# driver_power_AC.net
KiCad netlist of a schematic drawn in EAGLE
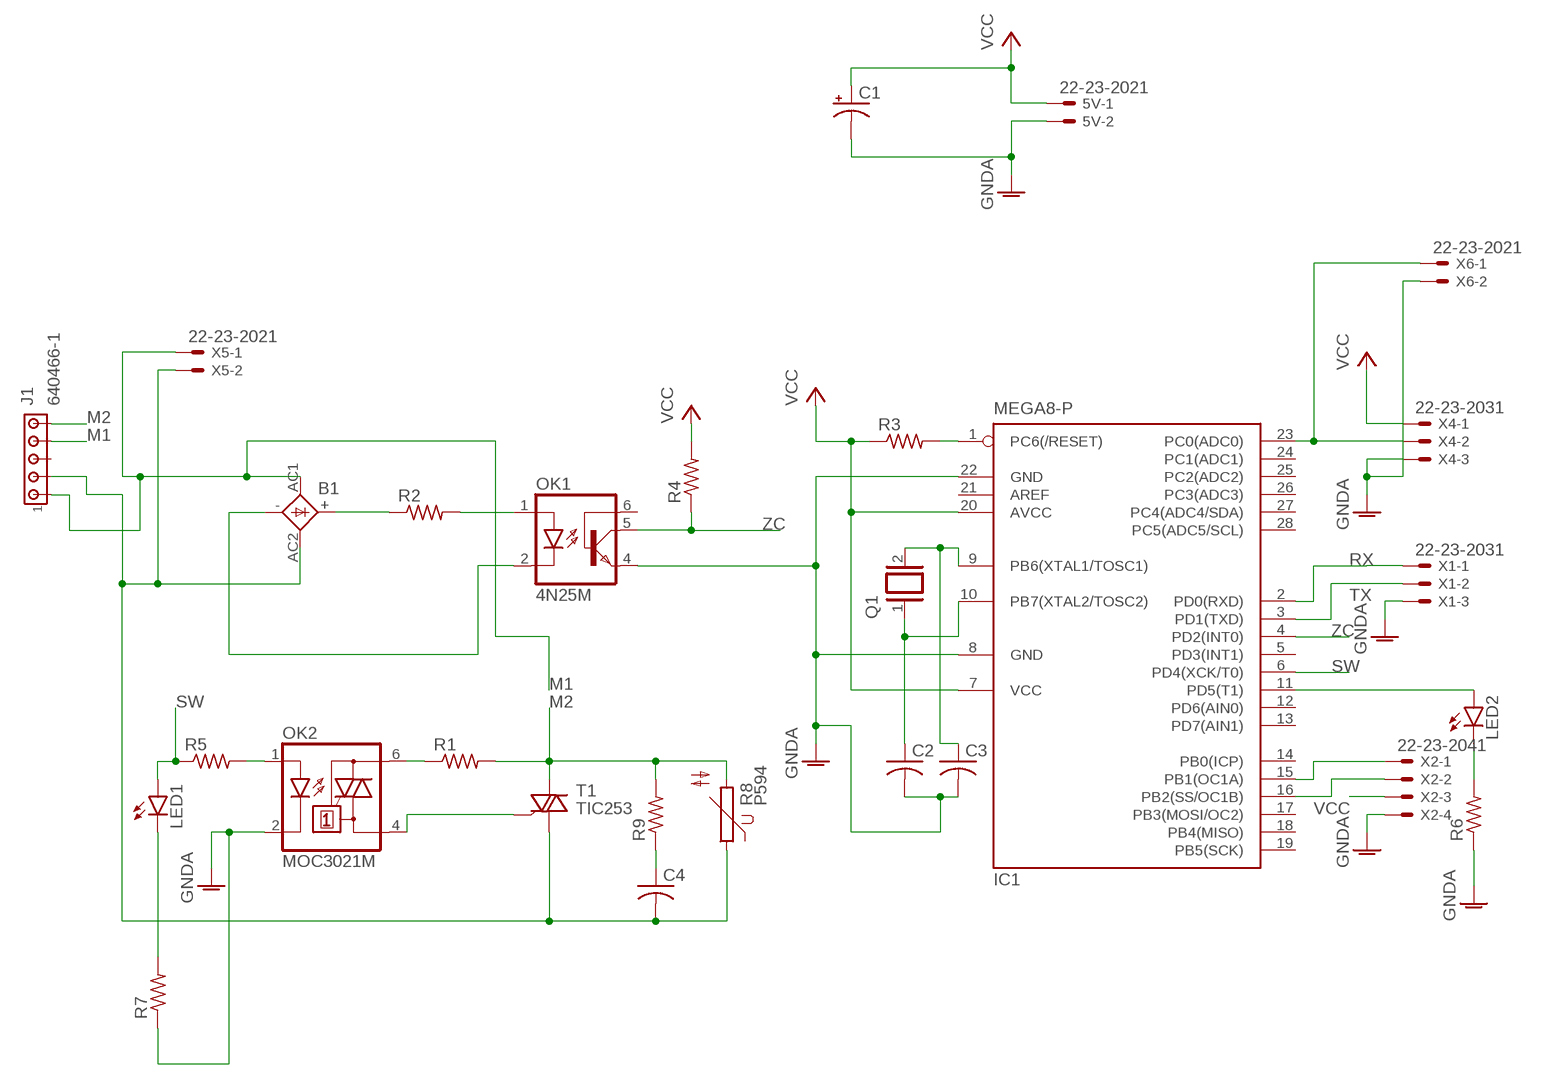
[diagram p0: schematic, sheet 1]

(export (version "E")
  (design (tool "Eeschema 10.0.6"))
  (components
    (comp (ref "5V")
      (value "22-23-2021")
      (footprint "eagle-import:22-23-2021")
      (fields (field (name "MF") "MOLEX"))
      (libsource (lib "eagle-import") (part "22-23-2021"))
    )
    (comp (ref "B1")
      (value "SKB")
      (footprint "eagle-import:SKB")
      (libsource (lib "eagle-import") (part "SKB"))
    )
    (comp (ref "C1")
      (value "CPOL-USE5-10.5")
      (footprint "eagle-import:E5-10,5")
      (libsource (lib "eagle-import") (part "CPOL-USE5-10.5"))
    )
    (comp (ref "C2")
      (value "C-US025-025X050")
      (footprint "eagle-import:C025-025X050")
      (libsource (lib "eagle-import") (part "C-US025-025X050"))
    )
    (comp (ref "C3")
      (value "C-US025-025X050")
      (footprint "eagle-import:C025-025X050")
      (libsource (lib "eagle-import") (part "C-US025-025X050"))
    )
    (comp (ref "C4")
      (value "C-US050-025X075")
      (footprint "eagle-import:C050-025X075")
      (libsource (lib "eagle-import") (part "C-US050-025X075"))
    )
    (comp (ref "IC1")
      (value "MEGA8-P")
      (footprint "eagle-import:DIL28-3")
      (libsource (lib "eagle-import") (part "MEGA8-P"))
    )
    (comp (ref "J1")
      (value "640466-1")
      (footprint "eagle-import:640466-1")
      (libsource (lib "eagle-import") (part "640466-1"))
    )
    (comp (ref "LED1")
      (value "LED3MM")
      (footprint "eagle-import:LED3MM")
      (libsource (lib "eagle-import") (part "LED3MM"))
    )
    (comp (ref "LED2")
      (value "LED3MM")
      (footprint "eagle-import:LED3MM")
      (libsource (lib "eagle-import") (part "LED3MM"))
    )
    (comp (ref "OK1")
      (value "4N25M")
      (footprint "eagle-import:DIL06")
      (fields (field (name "MPN") "4N25-M"))
      (libsource (lib "eagle-import") (part "4N?M25"))
    )
    (comp (ref "OK2")
      (value "MOC3021M")
      (footprint "eagle-import:DIL06")
      (fields (field (name "MF") "FAIRCHILD SEMICONDUCTOR") (field (name "MPN") "MOC3021-M"))
      (libsource (lib "eagle-import") (part "MOC30M21"))
    )
    (comp (ref "Q1")
      (value "XTAL/S")
      (footprint "eagle-import:QS")
      (libsource (lib "eagle-import") (part "XTAL/S"))
    )
    (comp (ref "R1")
      (value "R-US_0411/12")
      (footprint "eagle-import:0411_12")
      (libsource (lib "eagle-import") (part "R-US_0411/12"))
    )
    (comp (ref "R2")
      (value "R-US_0617/22")
      (footprint "eagle-import:0617_22")
      (libsource (lib "eagle-import") (part "R-US_0617/22"))
    )
    (comp (ref "R3")
      (value "R-US_0204/7")
      (footprint "eagle-import:0204_7")
      (libsource (lib "eagle-import") (part "R-US_0204/7"))
    )
    (comp (ref "R4")
      (value "R-US_0207/10")
      (footprint "eagle-import:0207_10")
      (libsource (lib "eagle-import") (part "R-US_0207/10"))
    )
    (comp (ref "R5")
      (value "R-US_0207/10")
      (footprint "eagle-import:0207_10")
      (libsource (lib "eagle-import") (part "R-US_0207/10"))
    )
    (comp (ref "R6")
      (value "R-US_0207/10")
      (footprint "eagle-import:0207_10")
      (libsource (lib "eagle-import") (part "R-US_0207/10"))
    )
    (comp (ref "R7")
      (value "R-US_0207/10")
      (footprint "eagle-import:0207_10")
      (libsource (lib "eagle-import") (part "R-US_0207/10"))
    )
    (comp (ref "R8")
      (value "P594")
      (footprint "eagle-import:P594")
      (libsource (lib "eagle-import") (part "P594"))
    )
    (comp (ref "R9")
      (value "R-US_0207/7")
      (footprint "eagle-import:0207_7")
      (libsource (lib "eagle-import") (part "R-US_0207/7"))
    )
    (comp (ref "T1")
      (value "TIC253")
      (footprint "eagle-import:TO218DS")
      (libsource (lib "eagle-import") (part "TIC253"))
    )
    (comp (ref "X1")
      (value "22-23-2031")
      (footprint "eagle-import:22-23-2031")
      (fields (field (name "MF") "MOLEX"))
      (libsource (lib "eagle-import") (part "22-23-2031"))
    )
    (comp (ref "X2")
      (value "22-23-2041")
      (footprint "eagle-import:22-23-2041")
      (fields (field (name "MF") "MOLEX"))
      (libsource (lib "eagle-import") (part "22-23-2041"))
    )
    (comp (ref "X4")
      (value "22-23-2031")
      (footprint "eagle-import:22-23-2031")
      (fields (field (name "MF") "MOLEX"))
      (libsource (lib "eagle-import") (part "22-23-2031"))
    )
    (comp (ref "X5")
      (value "22-23-2021")
      (footprint "eagle-import:22-23-2021")
      (fields (field (name "MF") "MOLEX"))
      (libsource (lib "eagle-import") (part "22-23-2021"))
    )
    (comp (ref "X6")
      (value "22-23-2021")
      (footprint "eagle-import:22-23-2021")
      (fields (field (name "MF") "MOLEX"))
      (libsource (lib "eagle-import") (part "22-23-2021"))
    )
  )
  (nets
    (net (code "1") (name "/M1") (class "Default")
      (node (ref "B1") (pin "AC1") (pinfunction "AC1_AC1") (pintype "passive"))
      (node (ref "J1") (pin "1") (pinfunction "1_1") (pintype "passive"))
      (node (ref "J1") (pin "4") (pinfunction "4_4") (pintype "passive"))
      (node (ref "X5") (pin "1") (pinfunction "S_1") (pintype "passive"))
    )
    (net (code "2") (name "/M2") (class "Default")
      (node (ref "J1") (pin "5") (pinfunction "5_5") (pintype "passive"))
      (node (ref "R1") (pin "2") (pinfunction "2_2") (pintype "passive"))
      (node (ref "R8") (pin "2") (pinfunction "2_2") (pintype "passive"))
      (node (ref "R9") (pin "2") (pinfunction "2_2") (pintype "passive"))
      (node (ref "T1") (pin "A2") (pinfunction "A2_A2") (pintype "passive"))
    )
    (net (code "3") (name "/RX") (class "Default")
      (node (ref "IC1") (pin "2") (pinfunction "PD0(RXD)_2") (pintype "bidirectional"))
      (node (ref "X1") (pin "1") (pinfunction "S_1") (pintype "passive"))
    )
    (net (code "4") (name "/SW") (class "Default")
      (node (ref "IC1") (pin "6") (pinfunction "PD4(XCK/T0)_6") (pintype "bidirectional"))
      (node (ref "LED1") (pin "A") (pinfunction "A_A") (pintype "passive"))
      (node (ref "R5") (pin "1") (pinfunction "1_1") (pintype "passive"))
    )
    (net (code "5") (name "/TX") (class "Default")
      (node (ref "IC1") (pin "3") (pinfunction "PD1(TXD)_3") (pintype "bidirectional"))
      (node (ref "X1") (pin "2") (pinfunction "S_2") (pintype "passive"))
    )
    (net (code "6") (name "/ZC") (class "Default")
      (node (ref "IC1") (pin "4") (pinfunction "PD2(INT0)_4") (pintype "bidirectional"))
      (node (ref "OK1") (pin "5") (pinfunction "COL_5") (pintype "passive"))
      (node (ref "R4") (pin "1") (pinfunction "1_1") (pintype "passive"))
    )
    (net (code "7") (name "GNDA") (class "Default")
      (node (ref "5V") (pin "2") (pinfunction "S_2") (pintype "passive"))
      (node (ref "C1") (pin "-") (pinfunction "-_-") (pintype "passive"))
      (node (ref "C2") (pin "2") (pinfunction "2_2") (pintype "passive"))
      (node (ref "C3") (pin "2") (pinfunction "2_2") (pintype "passive"))
      (node (ref "IC1") (pin "22") (pinfunction "GND_22") (pintype "power_in"))
      (node (ref "IC1") (pin "8") (pinfunction "GND_8") (pintype "power_in"))
      (node (ref "OK1") (pin "4") (pinfunction "EMI_4") (pintype "passive"))
      (node (ref "OK2") (pin "2") (pinfunction "C_2") (pintype "passive"))
      (node (ref "R6") (pin "1") (pinfunction "1_1") (pintype "passive"))
      (node (ref "R7") (pin "1") (pinfunction "1_1") (pintype "passive"))
      (node (ref "X1") (pin "3") (pinfunction "S_3") (pintype "passive"))
      (node (ref "X2") (pin "4") (pinfunction "S_4") (pintype "passive"))
      (node (ref "X4") (pin "3") (pinfunction "S_3") (pintype "passive"))
      (node (ref "X6") (pin "2") (pinfunction "S_2") (pintype "passive"))
    )
    (net (code "8") (name "Net-(B1-Pad+)") (class "Default")
      (node (ref "B1") (pin "+") (pinfunction "+_+") (pintype "passive"))
      (node (ref "R2") (pin "1") (pinfunction "1_1") (pintype "passive"))
    )
    (net (code "9") (name "Net-(C4-Pad1)") (class "Default")
      (node (ref "C4") (pin "1") (pinfunction "1_1") (pintype "passive"))
      (node (ref "R9") (pin "1") (pinfunction "1_1") (pintype "passive"))
    )
    (net (code "10") (name "Net-(IC1-PB1(OC1A))") (class "Default")
      (node (ref "IC1") (pin "15") (pinfunction "PB1(OC1A)_15") (pintype "bidirectional"))
      (node (ref "X2") (pin "1") (pinfunction "S_1") (pintype "passive"))
    )
    (net (code "11") (name "Net-(IC1-PB2(SS{slash}OC1B))") (class "Default")
      (node (ref "IC1") (pin "16") (pinfunction "PB2(SS/OC1B)_16") (pintype "bidirectional"))
      (node (ref "X2") (pin "2") (pinfunction "S_2") (pintype "passive"))
    )
    (net (code "12") (name "Net-(IC1-PB6(XTAL1{slash}TOSC1))") (class "Default")
      (node (ref "C3") (pin "1") (pinfunction "1_1") (pintype "passive"))
      (node (ref "IC1") (pin "9") (pinfunction "PB6(XTAL1/TOSC1)_9") (pintype "bidirectional"))
      (node (ref "Q1") (pin "2") (pinfunction "2_2") (pintype "passive"))
    )
    (net (code "13") (name "Net-(IC1-PB7(XTAL2{slash}TOSC2))") (class "Default")
      (node (ref "C2") (pin "1") (pinfunction "1_1") (pintype "passive"))
      (node (ref "IC1") (pin "10") (pinfunction "PB7(XTAL2/TOSC2)_10") (pintype "bidirectional"))
      (node (ref "Q1") (pin "1") (pinfunction "1_1") (pintype "passive"))
    )
    (net (code "14") (name "Net-(IC1-PC0(ADC0))") (class "Default")
      (node (ref "IC1") (pin "23") (pinfunction "PC0(ADC0)_23") (pintype "bidirectional"))
      (node (ref "X4") (pin "2") (pinfunction "S_2") (pintype "passive"))
      (node (ref "X6") (pin "1") (pinfunction "S_1") (pintype "passive"))
    )
    (net (code "15") (name "Net-(IC1-PC6({slash}RESET))") (class "Default")
      (node (ref "IC1") (pin "1") (pinfunction "PC6(/RESET)_1") (pintype "bidirectional"))
      (node (ref "R3") (pin "2") (pinfunction "2_2") (pintype "passive"))
    )
    (net (code "16") (name "Net-(IC1-PD5(T1))") (class "Default")
      (node (ref "IC1") (pin "11") (pinfunction "PD5(T1)_11") (pintype "bidirectional"))
      (node (ref "LED2") (pin "A") (pinfunction "A_A") (pintype "passive"))
    )
    (net (code "17") (name "Net-(LED1-C)") (class "Default")
      (node (ref "LED1") (pin "K") (pinfunction "C_K") (pintype "passive"))
      (node (ref "R7") (pin "2") (pinfunction "2_2") (pintype "passive"))
    )
    (net (code "18") (name "Net-(LED2-C)") (class "Default")
      (node (ref "LED2") (pin "K") (pinfunction "C_K") (pintype "passive"))
      (node (ref "R6") (pin "2") (pinfunction "2_2") (pintype "passive"))
    )
    (net (code "19") (name "Net-(OK1-A)") (class "Default")
      (node (ref "OK1") (pin "1") (pinfunction "A_1") (pintype "passive"))
      (node (ref "R2") (pin "2") (pinfunction "2_2") (pintype "passive"))
    )
    (net (code "20") (name "Net-(OK1-C)") (class "Default")
      (node (ref "B1") (pin "-") (pinfunction "-_-") (pintype "passive"))
      (node (ref "OK1") (pin "2") (pinfunction "C_2") (pintype "passive"))
    )
    (net (code "21") (name "Net-(OK2-A)") (class "Default")
      (node (ref "OK2") (pin "1") (pinfunction "A_1") (pintype "passive"))
      (node (ref "R5") (pin "2") (pinfunction "2_2") (pintype "passive"))
    )
    (net (code "22") (name "Net-(OK2-A1)") (class "Default")
      (node (ref "OK2") (pin "4") (pinfunction "A1_4") (pintype "passive"))
      (node (ref "T1") (pin "G") (pinfunction "G_G") (pintype "passive"))
    )
    (net (code "23") (name "Net-(OK2-A2)") (class "Default")
      (node (ref "OK2") (pin "6") (pinfunction "A2_6") (pintype "passive"))
      (node (ref "R1") (pin "1") (pinfunction "1_1") (pintype "passive"))
    )
    (net (code "24") (name "Net-(X5B-S)") (class "Default")
      (node (ref "B1") (pin "AC2") (pinfunction "AC2_AC2") (pintype "passive"))
      (node (ref "C4") (pin "2") (pinfunction "2_2") (pintype "passive"))
      (node (ref "J1") (pin "2") (pinfunction "2_2") (pintype "passive"))
      (node (ref "R8") (pin "1") (pinfunction "1_1") (pintype "passive"))
      (node (ref "T1") (pin "A1") (pinfunction "A1_A1") (pintype "passive"))
      (node (ref "X5") (pin "2") (pinfunction "S_2") (pintype "passive"))
    )
    (net (code "25") (name "VCC") (class "Default")
      (node (ref "5V") (pin "1") (pinfunction "S_1") (pintype "passive"))
      (node (ref "C1") (pin "+") (pinfunction "+_+") (pintype "passive"))
      (node (ref "IC1") (pin "20") (pinfunction "AVCC_20") (pintype "power_in"))
      (node (ref "IC1") (pin "7") (pinfunction "VCC_7") (pintype "power_in"))
      (node (ref "R3") (pin "1") (pinfunction "1_1") (pintype "passive"))
      (node (ref "R4") (pin "2") (pinfunction "2_2") (pintype "passive"))
      (node (ref "X2") (pin "3") (pinfunction "S_3") (pintype "passive"))
      (node (ref "X4") (pin "1") (pinfunction "S_1") (pintype "passive"))
    )
    (net (code "26") (name "unconnected-(IC1-AREF-Pad21)") (class "Default")
      (node (ref "IC1") (pin "21") (pinfunction "AREF_21") (pintype "passive"))
    )
    (net (code "27") (name "unconnected-(IC1-PB0(ICP)-Pad14)") (class "Default")
      (node (ref "IC1") (pin "14") (pinfunction "PB0(ICP)_14") (pintype "bidirectional"))
    )
    (net (code "28") (name "unconnected-(IC1-PB3(MOSI{slash}OC2)-Pad17)") (class "Default")
      (node (ref "IC1") (pin "17") (pinfunction "PB3(MOSI/OC2)_17") (pintype "bidirectional"))
    )
    (net (code "29") (name "unconnected-(IC1-PB4(MISO)-Pad18)") (class "Default")
      (node (ref "IC1") (pin "18") (pinfunction "PB4(MISO)_18") (pintype "bidirectional"))
    )
    (net (code "30") (name "unconnected-(IC1-PB5(SCK)-Pad19)") (class "Default")
      (node (ref "IC1") (pin "19") (pinfunction "PB5(SCK)_19") (pintype "bidirectional"))
    )
    (net (code "31") (name "unconnected-(IC1-PC1(ADC1)-Pad24)") (class "Default")
      (node (ref "IC1") (pin "24") (pinfunction "PC1(ADC1)_24") (pintype "bidirectional"))
    )
    (net (code "32") (name "unconnected-(IC1-PC2(ADC2)-Pad25)") (class "Default")
      (node (ref "IC1") (pin "25") (pinfunction "PC2(ADC2)_25") (pintype "bidirectional"))
    )
    (net (code "33") (name "unconnected-(IC1-PC3(ADC3)-Pad26)") (class "Default")
      (node (ref "IC1") (pin "26") (pinfunction "PC3(ADC3)_26") (pintype "bidirectional"))
    )
    (net (code "34") (name "unconnected-(IC1-PC4(ADC4{slash}SDA)-Pad27)") (class "Default")
      (node (ref "IC1") (pin "27") (pinfunction "PC4(ADC4/SDA)_27") (pintype "bidirectional"))
    )
    (net (code "35") (name "unconnected-(IC1-PC5(ADC5{slash}SCL)-Pad28)") (class "Default")
      (node (ref "IC1") (pin "28") (pinfunction "PC5(ADC5/SCL)_28") (pintype "bidirectional"))
    )
    (net (code "36") (name "unconnected-(IC1-PD3(INT1)-Pad5)") (class "Default")
      (node (ref "IC1") (pin "5") (pinfunction "PD3(INT1)_5") (pintype "bidirectional"))
    )
    (net (code "37") (name "unconnected-(IC1-PD6(AIN0)-Pad12)") (class "Default")
      (node (ref "IC1") (pin "12") (pinfunction "PD6(AIN0)_12") (pintype "bidirectional"))
    )
    (net (code "38") (name "unconnected-(IC1-PD7(AIN1)-Pad13)") (class "Default")
      (node (ref "IC1") (pin "13") (pinfunction "PD7(AIN1)_13") (pintype "bidirectional"))
    )
    (net (code "39") (name "unconnected-(J1-Pad3)") (class "Default")
      (node (ref "J1") (pin "3") (pinfunction "3_3") (pintype "passive"))
    )
    (net (code "40") (name "unconnected-(OK1-BAS-Pad6)") (class "Default")
      (node (ref "OK1") (pin "6") (pinfunction "BAS_6") (pintype "passive"))
    )
  )
)
